# Carte_Keil_Emile_can_v0.net
KiCad netlist of a schematic drawn in Altium Designer
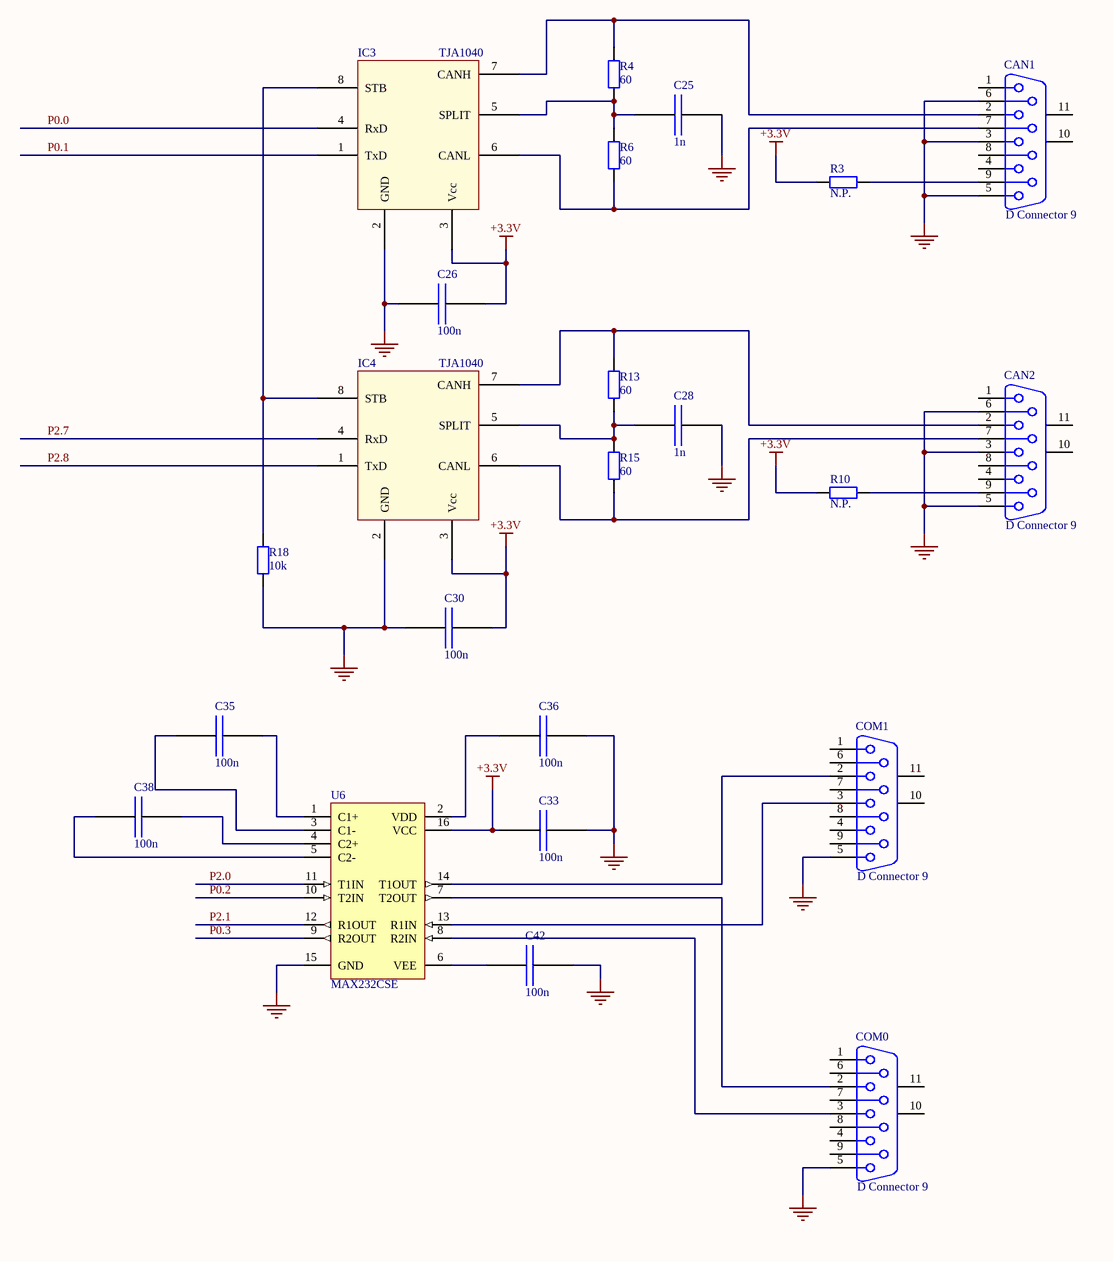
[diagram p0: Carte_Keil_Emile_can_v0.SchDoc]

(export (version "E")
  (design (tool "Eeschema 10.0.6"))
  (components
    (comp (ref "C25") (value "1n") (footprint "Res_1206") (libsource (lib "LibEmile") (part "Capa_1206")))
    (comp (ref "C26") (value "100n") (footprint "Res_1206") (libsource (lib "LibEmile") (part "Capa_1206")))
    (comp (ref "C28") (value "1n") (footprint "Res_1206") (libsource (lib "LibEmile") (part "Capa_1206")))
    (comp (ref "C30") (value "100n") (footprint "Res_1206") (libsource (lib "LibEmile") (part "Capa_1206")))
    (comp (ref "C33") (value "100n") (footprint "Res_1206") (libsource (lib "LibEmile") (part "Capa_1206")))
    (comp (ref "C35") (value "100n") (footprint "Res_1206") (libsource (lib "LibEmile") (part "Capa_1206")))
    (comp (ref "C36") (value "100n") (footprint "Res_1206") (libsource (lib "LibEmile") (part "Capa_1206")))
    (comp (ref "C38") (value "100n") (footprint "Res_1206") (libsource (lib "LibEmile") (part "Capa_1206")))
    (comp (ref "C42") (value "100n") (footprint "Res_1206") (libsource (lib "LibEmile") (part "Capa_1206")))
    (comp (ref "CAN1")
      (value "D Connector 9")
      (footprint "DSUB1.385-2H9")
      (description "Receptacle Assembly, 9 Position, Right Angle")
      (fields (field (name "PUBLISHER") "Altium Limited"))
      (libsource (lib "Miscellaneous Connectors") (part "D Connector 9"))
    )
    (comp (ref "CAN2")
      (value "D Connector 9")
      (footprint "DSUB1.385-2H9")
      (description "Receptacle Assembly, 9 Position, Right Angle")
      (fields (field (name "PUBLISHER") "Altium Limited"))
      (libsource (lib "Miscellaneous Connectors") (part "D Connector 9"))
    )
    (comp (ref "COM0")
      (value "D Connector 9")
      (footprint "DSUB1.385-2H9")
      (description "Receptacle Assembly, 9 Position, Right Angle")
      (fields (field (name "PUBLISHER") "Altium Limited"))
      (libsource (lib "Miscellaneous Connectors") (part "D Connector 9"))
    )
    (comp (ref "COM1")
      (value "D Connector 9")
      (footprint "DSUB1.385-2H9")
      (description "Receptacle Assembly, 9 Position, Right Angle")
      (fields (field (name "PUBLISHER") "Altium Limited"))
      (libsource (lib "Miscellaneous Connectors") (part "D Connector 9"))
    )
    (comp (ref "IC3")
      (value "TJA1040")
      (footprint "SO-G8")
      (description "CAN bus transceiver")
      (libsource (lib "LibEmile") (part "TJA1040"))
    )
    (comp (ref "IC4")
      (value "TJA1040")
      (footprint "SO-G8")
      (description "CAN bus transceiver")
      (libsource (lib "LibEmile") (part "TJA1040"))
    )
    (comp (ref "R3")
      (value "N.P.")
      (footprint "CR3216-1206")
      (description "Resistance")
      (fields (field (name "Comment") "Res") (field (name "PUBLISHER") "Altium Limited"))
      (libsource (lib "") (part "Res_1"))
    )
    (comp (ref "R4")
      (value "60")
      (footprint "CR3216-1206")
      (description "Resistance")
      (fields (field (name "Comment") "Res") (field (name "PUBLISHER") "Altium Limited"))
      (libsource (lib "Gamel_Trophy_v2re6") (part "Res"))
    )
    (comp (ref "R6")
      (value "60")
      (footprint "CR3216-1206")
      (description "Resistance")
      (fields (field (name "Comment") "Res") (field (name "PUBLISHER") "Altium Limited"))
      (libsource (lib "Gamel_Trophy_v2re6") (part "Res"))
    )
    (comp (ref "R10")
      (value "N.P.")
      (footprint "CR3216-1206")
      (description "Resistance")
      (fields (field (name "Comment") "Res") (field (name "PUBLISHER") "Altium Limited"))
      (libsource (lib "") (part "Res_1"))
    )
    (comp (ref "R13")
      (value "60")
      (footprint "CR3216-1206")
      (description "Resistance")
      (fields (field (name "Comment") "Res") (field (name "PUBLISHER") "Altium Limited"))
      (libsource (lib "Gamel_Trophy_v2re6") (part "Res"))
    )
    (comp (ref "R15")
      (value "60")
      (footprint "CR3216-1206")
      (description "Resistance")
      (fields (field (name "Comment") "Res") (field (name "PUBLISHER") "Altium Limited"))
      (libsource (lib "Gamel_Trophy_v2re6") (part "Res"))
    )
    (comp (ref "R18")
      (value "10k")
      (footprint "CR3216-1206")
      (description "Resistance")
      (fields (field (name "Comment") "Res") (field (name "PUBLISHER") "Altium Limited"))
      (libsource (lib "Gamel_Trophy_v2re6") (part "Res"))
    )
    (comp (ref "U6")
      (value "MAX232CSE")
      (footprint "NSO16")
      (description "+5V Powered, Multi-Channel RS-232 Driver/Receiver")
      (fields (field (name "PUBLISHER") "Altium Limited"))
      (libsource (lib "Maxim Communication Transceiver") (part "MAX232CSE"))
    )
  )
  (nets
    (net (code "1") (name "+3.3V") (class "Default")
      (node (ref "C26") (pin "2") (pinfunction "2_2") (pintype "passive"))
      (node (ref "C30") (pin "2") (pinfunction "2_2") (pintype "passive"))
      (node (ref "C33") (pin "1") (pinfunction "1_1") (pintype "passive"))
      (node (ref "IC3") (pin "3") (pinfunction "Vcc_3") (pintype "passive"))
      (node (ref "IC4") (pin "3") (pinfunction "Vcc_3") (pintype "passive"))
      (node (ref "R10") (pin "2") (pinfunction "2_2") (pintype "passive"))
      (node (ref "R3") (pin "2") (pinfunction "2_2") (pintype "passive"))
      (node (ref "U6") (pin "16") (pinfunction "VCC_16") (pintype "power_in"))
    )
    (net (code "2") (name "/P0.0") (class "Default")
      (node (ref "IC3") (pin "4") (pinfunction "RxD_4") (pintype "passive"))
    )
    (net (code "3") (name "/P0.1") (class "Default")
      (node (ref "IC3") (pin "1") (pinfunction "TxD_1") (pintype "passive"))
    )
    (net (code "4") (name "/P0.2") (class "Default")
      (node (ref "U6") (pin "10") (pinfunction "T2IN_10") (pintype "input"))
    )
    (net (code "5") (name "/P0.3") (class "Default")
      (node (ref "U6") (pin "9") (pinfunction "R2OUT_9") (pintype "output"))
    )
    (net (code "6") (name "/P2.0") (class "Default")
      (node (ref "U6") (pin "11") (pinfunction "T1IN_11") (pintype "input"))
    )
    (net (code "7") (name "/P2.1") (class "Default")
      (node (ref "U6") (pin "12") (pinfunction "R1OUT_12") (pintype "output"))
    )
    (net (code "8") (name "/P2.7") (class "Default")
      (node (ref "IC4") (pin "4") (pinfunction "RxD_4") (pintype "passive"))
    )
    (net (code "9") (name "/P2.8") (class "Default")
      (node (ref "IC4") (pin "1") (pinfunction "TxD_1") (pintype "passive"))
    )
    (net (code "10") (name "GND") (class "Default")
      (node (ref "C25") (pin "2") (pinfunction "2_2") (pintype "passive"))
      (node (ref "C26") (pin "1") (pinfunction "1_1") (pintype "passive"))
      (node (ref "C28") (pin "2") (pinfunction "2_2") (pintype "passive"))
      (node (ref "C30") (pin "1") (pinfunction "1_1") (pintype "passive"))
      (node (ref "C33") (pin "2") (pinfunction "2_2") (pintype "passive"))
      (node (ref "C36") (pin "2") (pinfunction "2_2") (pintype "passive"))
      (node (ref "C42") (pin "2") (pinfunction "2_2") (pintype "passive"))
      (node (ref "CAN1") (pin "3") (pinfunction "3_3") (pintype "passive"))
      (node (ref "CAN1") (pin "5") (pinfunction "5_5") (pintype "passive"))
      (node (ref "CAN1") (pin "6") (pinfunction "6_6") (pintype "passive"))
      (node (ref "CAN2") (pin "3") (pinfunction "3_3") (pintype "passive"))
      (node (ref "CAN2") (pin "5") (pinfunction "5_5") (pintype "passive"))
      (node (ref "CAN2") (pin "6") (pinfunction "6_6") (pintype "passive"))
      (node (ref "COM0") (pin "5") (pinfunction "5_5") (pintype "passive"))
      (node (ref "COM1") (pin "5") (pinfunction "5_5") (pintype "passive"))
      (node (ref "IC3") (pin "2") (pinfunction "GND_2") (pintype "passive"))
      (node (ref "IC4") (pin "2") (pinfunction "GND_2") (pintype "passive"))
      (node (ref "R18") (pin "2") (pinfunction "2_2") (pintype "passive"))
      (node (ref "U6") (pin "15") (pinfunction "GND_15") (pintype "power_in"))
    )
    (net (code "11") (name "Net-(CAN1-Pad9)") (class "Default")
      (node (ref "CAN1") (pin "9") (pinfunction "9_9") (pintype "passive"))
      (node (ref "R3") (pin "1") (pinfunction "1_1") (pintype "passive"))
    )
    (net (code "12") (name "Net-(CAN2-Pad9)") (class "Default")
      (node (ref "CAN2") (pin "9") (pinfunction "9_9") (pintype "passive"))
      (node (ref "R10") (pin "1") (pinfunction "1_1") (pintype "passive"))
    )
    (net (code "13") (name "Net-(IC3-CANH)") (class "Default")
      (node (ref "CAN1") (pin "2") (pinfunction "2_2") (pintype "passive"))
      (node (ref "IC3") (pin "7") (pinfunction "CANH_7") (pintype "passive"))
      (node (ref "R4") (pin "1") (pinfunction "1_1") (pintype "passive"))
    )
    (net (code "14") (name "Net-(IC3-CANL)") (class "Default")
      (node (ref "CAN1") (pin "7") (pinfunction "7_7") (pintype "passive"))
      (node (ref "IC3") (pin "6") (pinfunction "CANL_6") (pintype "passive"))
      (node (ref "R6") (pin "2") (pinfunction "2_2") (pintype "passive"))
    )
    (net (code "15") (name "Net-(IC3-SPLIT)") (class "Default")
      (node (ref "C25") (pin "1") (pinfunction "1_1") (pintype "passive"))
      (node (ref "IC3") (pin "5") (pinfunction "SPLIT_5") (pintype "passive"))
      (node (ref "R4") (pin "2") (pinfunction "2_2") (pintype "passive"))
      (node (ref "R6") (pin "1") (pinfunction "1_1") (pintype "passive"))
    )
    (net (code "16") (name "Net-(IC3-STB)") (class "Default")
      (node (ref "IC3") (pin "8") (pinfunction "STB_8") (pintype "passive"))
      (node (ref "IC4") (pin "8") (pinfunction "STB_8") (pintype "passive"))
      (node (ref "R18") (pin "1") (pinfunction "1_1") (pintype "passive"))
    )
    (net (code "17") (name "Net-(IC4-CANH)") (class "Default")
      (node (ref "CAN2") (pin "2") (pinfunction "2_2") (pintype "passive"))
      (node (ref "IC4") (pin "7") (pinfunction "CANH_7") (pintype "passive"))
      (node (ref "R13") (pin "1") (pinfunction "1_1") (pintype "passive"))
    )
    (net (code "18") (name "Net-(IC4-CANL)") (class "Default")
      (node (ref "CAN2") (pin "7") (pinfunction "7_7") (pintype "passive"))
      (node (ref "IC4") (pin "6") (pinfunction "CANL_6") (pintype "passive"))
      (node (ref "R15") (pin "2") (pinfunction "2_2") (pintype "passive"))
    )
    (net (code "19") (name "Net-(IC4-SPLIT)") (class "Default")
      (node (ref "C28") (pin "1") (pinfunction "1_1") (pintype "passive"))
      (node (ref "IC4") (pin "5") (pinfunction "SPLIT_5") (pintype "passive"))
      (node (ref "R13") (pin "2") (pinfunction "2_2") (pintype "passive"))
      (node (ref "R15") (pin "1") (pinfunction "1_1") (pintype "passive"))
    )
    (net (code "20") (name "Net-(U6-C1+)") (class "Default")
      (node (ref "C35") (pin "2") (pinfunction "2_2") (pintype "passive"))
      (node (ref "U6") (pin "1") (pinfunction "C1+_1") (pintype "passive"))
    )
    (net (code "21") (name "Net-(U6-C1-)") (class "Default")
      (node (ref "C35") (pin "1") (pinfunction "1_1") (pintype "passive"))
      (node (ref "U6") (pin "3") (pinfunction "C1-_3") (pintype "passive"))
    )
    (net (code "22") (name "Net-(U6-C2+)") (class "Default")
      (node (ref "C38") (pin "2") (pinfunction "2_2") (pintype "passive"))
      (node (ref "U6") (pin "4") (pinfunction "C2+_4") (pintype "passive"))
    )
    (net (code "23") (name "Net-(U6-C2-)") (class "Default")
      (node (ref "C38") (pin "1") (pinfunction "1_1") (pintype "passive"))
      (node (ref "U6") (pin "5") (pinfunction "C2-_5") (pintype "passive"))
    )
    (net (code "24") (name "Net-(U6-R1IN)") (class "Default")
      (node (ref "COM1") (pin "3") (pinfunction "3_3") (pintype "passive"))
      (node (ref "U6") (pin "13") (pinfunction "R1IN_13") (pintype "input"))
    )
    (net (code "25") (name "Net-(U6-R2IN)") (class "Default")
      (node (ref "COM0") (pin "3") (pinfunction "3_3") (pintype "passive"))
      (node (ref "U6") (pin "8") (pinfunction "R2IN_8") (pintype "input"))
    )
    (net (code "26") (name "Net-(U6-T1OUT)") (class "Default")
      (node (ref "COM1") (pin "2") (pinfunction "2_2") (pintype "passive"))
      (node (ref "U6") (pin "14") (pinfunction "T1OUT_14") (pintype "output"))
    )
    (net (code "27") (name "Net-(U6-T2OUT)") (class "Default")
      (node (ref "COM0") (pin "2") (pinfunction "2_2") (pintype "passive"))
      (node (ref "U6") (pin "7") (pinfunction "T2OUT_7") (pintype "output"))
    )
    (net (code "28") (name "Net-(U6-VDD)") (class "Default")
      (node (ref "C36") (pin "1") (pinfunction "1_1") (pintype "passive"))
      (node (ref "U6") (pin "2") (pinfunction "VDD_2") (pintype "power_in"))
    )
    (net (code "29") (name "Net-(U6-VEE)") (class "Default")
      (node (ref "C42") (pin "1") (pinfunction "1_1") (pintype "passive"))
      (node (ref "U6") (pin "6") (pinfunction "VEE_6") (pintype "power_in"))
    )
    (net (code "30") (name "unconnected-(CAN1-MH1-Pad10)") (class "Default")
      (node (ref "CAN1") (pin "10") (pinfunction "MH1_10") (pintype "passive"))
    )
    (net (code "31") (name "unconnected-(CAN1-MH2-Pad11)") (class "Default")
      (node (ref "CAN1") (pin "11") (pinfunction "MH2_11") (pintype "passive"))
    )
    (net (code "32") (name "unconnected-(CAN1-Pad1)") (class "Default")
      (node (ref "CAN1") (pin "1") (pinfunction "1_1") (pintype "passive"))
    )
    (net (code "33") (name "unconnected-(CAN1-Pad4)") (class "Default")
      (node (ref "CAN1") (pin "4") (pinfunction "4_4") (pintype "passive"))
    )
    (net (code "34") (name "unconnected-(CAN1-Pad8)") (class "Default")
      (node (ref "CAN1") (pin "8") (pinfunction "8_8") (pintype "passive"))
    )
    (net (code "35") (name "unconnected-(CAN2-MH1-Pad10)") (class "Default")
      (node (ref "CAN2") (pin "10") (pinfunction "MH1_10") (pintype "passive"))
    )
    (net (code "36") (name "unconnected-(CAN2-MH2-Pad11)") (class "Default")
      (node (ref "CAN2") (pin "11") (pinfunction "MH2_11") (pintype "passive"))
    )
    (net (code "37") (name "unconnected-(CAN2-Pad1)") (class "Default")
      (node (ref "CAN2") (pin "1") (pinfunction "1_1") (pintype "passive"))
    )
    (net (code "38") (name "unconnected-(CAN2-Pad4)") (class "Default")
      (node (ref "CAN2") (pin "4") (pinfunction "4_4") (pintype "passive"))
    )
    (net (code "39") (name "unconnected-(CAN2-Pad8)") (class "Default")
      (node (ref "CAN2") (pin "8") (pinfunction "8_8") (pintype "passive"))
    )
    (net (code "40") (name "unconnected-(COM0-MH1-Pad10)") (class "Default")
      (node (ref "COM0") (pin "10") (pinfunction "MH1_10") (pintype "passive"))
    )
    (net (code "41") (name "unconnected-(COM0-MH2-Pad11)") (class "Default")
      (node (ref "COM0") (pin "11") (pinfunction "MH2_11") (pintype "passive"))
    )
    (net (code "42") (name "unconnected-(COM0-Pad1)") (class "Default")
      (node (ref "COM0") (pin "1") (pinfunction "1_1") (pintype "passive"))
    )
    (net (code "43") (name "unconnected-(COM0-Pad4)") (class "Default")
      (node (ref "COM0") (pin "4") (pinfunction "4_4") (pintype "passive"))
    )
    (net (code "44") (name "unconnected-(COM0-Pad6)") (class "Default")
      (node (ref "COM0") (pin "6") (pinfunction "6_6") (pintype "passive"))
    )
    (net (code "45") (name "unconnected-(COM0-Pad7)") (class "Default")
      (node (ref "COM0") (pin "7") (pinfunction "7_7") (pintype "passive"))
    )
    (net (code "46") (name "unconnected-(COM0-Pad8)") (class "Default")
      (node (ref "COM0") (pin "8") (pinfunction "8_8") (pintype "passive"))
    )
    (net (code "47") (name "unconnected-(COM0-Pad9)") (class "Default")
      (node (ref "COM0") (pin "9") (pinfunction "9_9") (pintype "passive"))
    )
    (net (code "48") (name "unconnected-(COM1-MH1-Pad10)") (class "Default")
      (node (ref "COM1") (pin "10") (pinfunction "MH1_10") (pintype "passive"))
    )
    (net (code "49") (name "unconnected-(COM1-MH2-Pad11)") (class "Default")
      (node (ref "COM1") (pin "11") (pinfunction "MH2_11") (pintype "passive"))
    )
    (net (code "50") (name "unconnected-(COM1-Pad1)") (class "Default")
      (node (ref "COM1") (pin "1") (pinfunction "1_1") (pintype "passive"))
    )
    (net (code "51") (name "unconnected-(COM1-Pad4)") (class "Default")
      (node (ref "COM1") (pin "4") (pinfunction "4_4") (pintype "passive"))
    )
    (net (code "52") (name "unconnected-(COM1-Pad6)") (class "Default")
      (node (ref "COM1") (pin "6") (pinfunction "6_6") (pintype "passive"))
    )
    (net (code "53") (name "unconnected-(COM1-Pad7)") (class "Default")
      (node (ref "COM1") (pin "7") (pinfunction "7_7") (pintype "passive"))
    )
    (net (code "54") (name "unconnected-(COM1-Pad8)") (class "Default")
      (node (ref "COM1") (pin "8") (pinfunction "8_8") (pintype "passive"))
    )
    (net (code "55") (name "unconnected-(COM1-Pad9)") (class "Default")
      (node (ref "COM1") (pin "9") (pinfunction "9_9") (pintype "passive"))
    )
  )
)
